# IMD_AMS_Latch.net
KiCad netlist of a schematic drawn in EAGLE
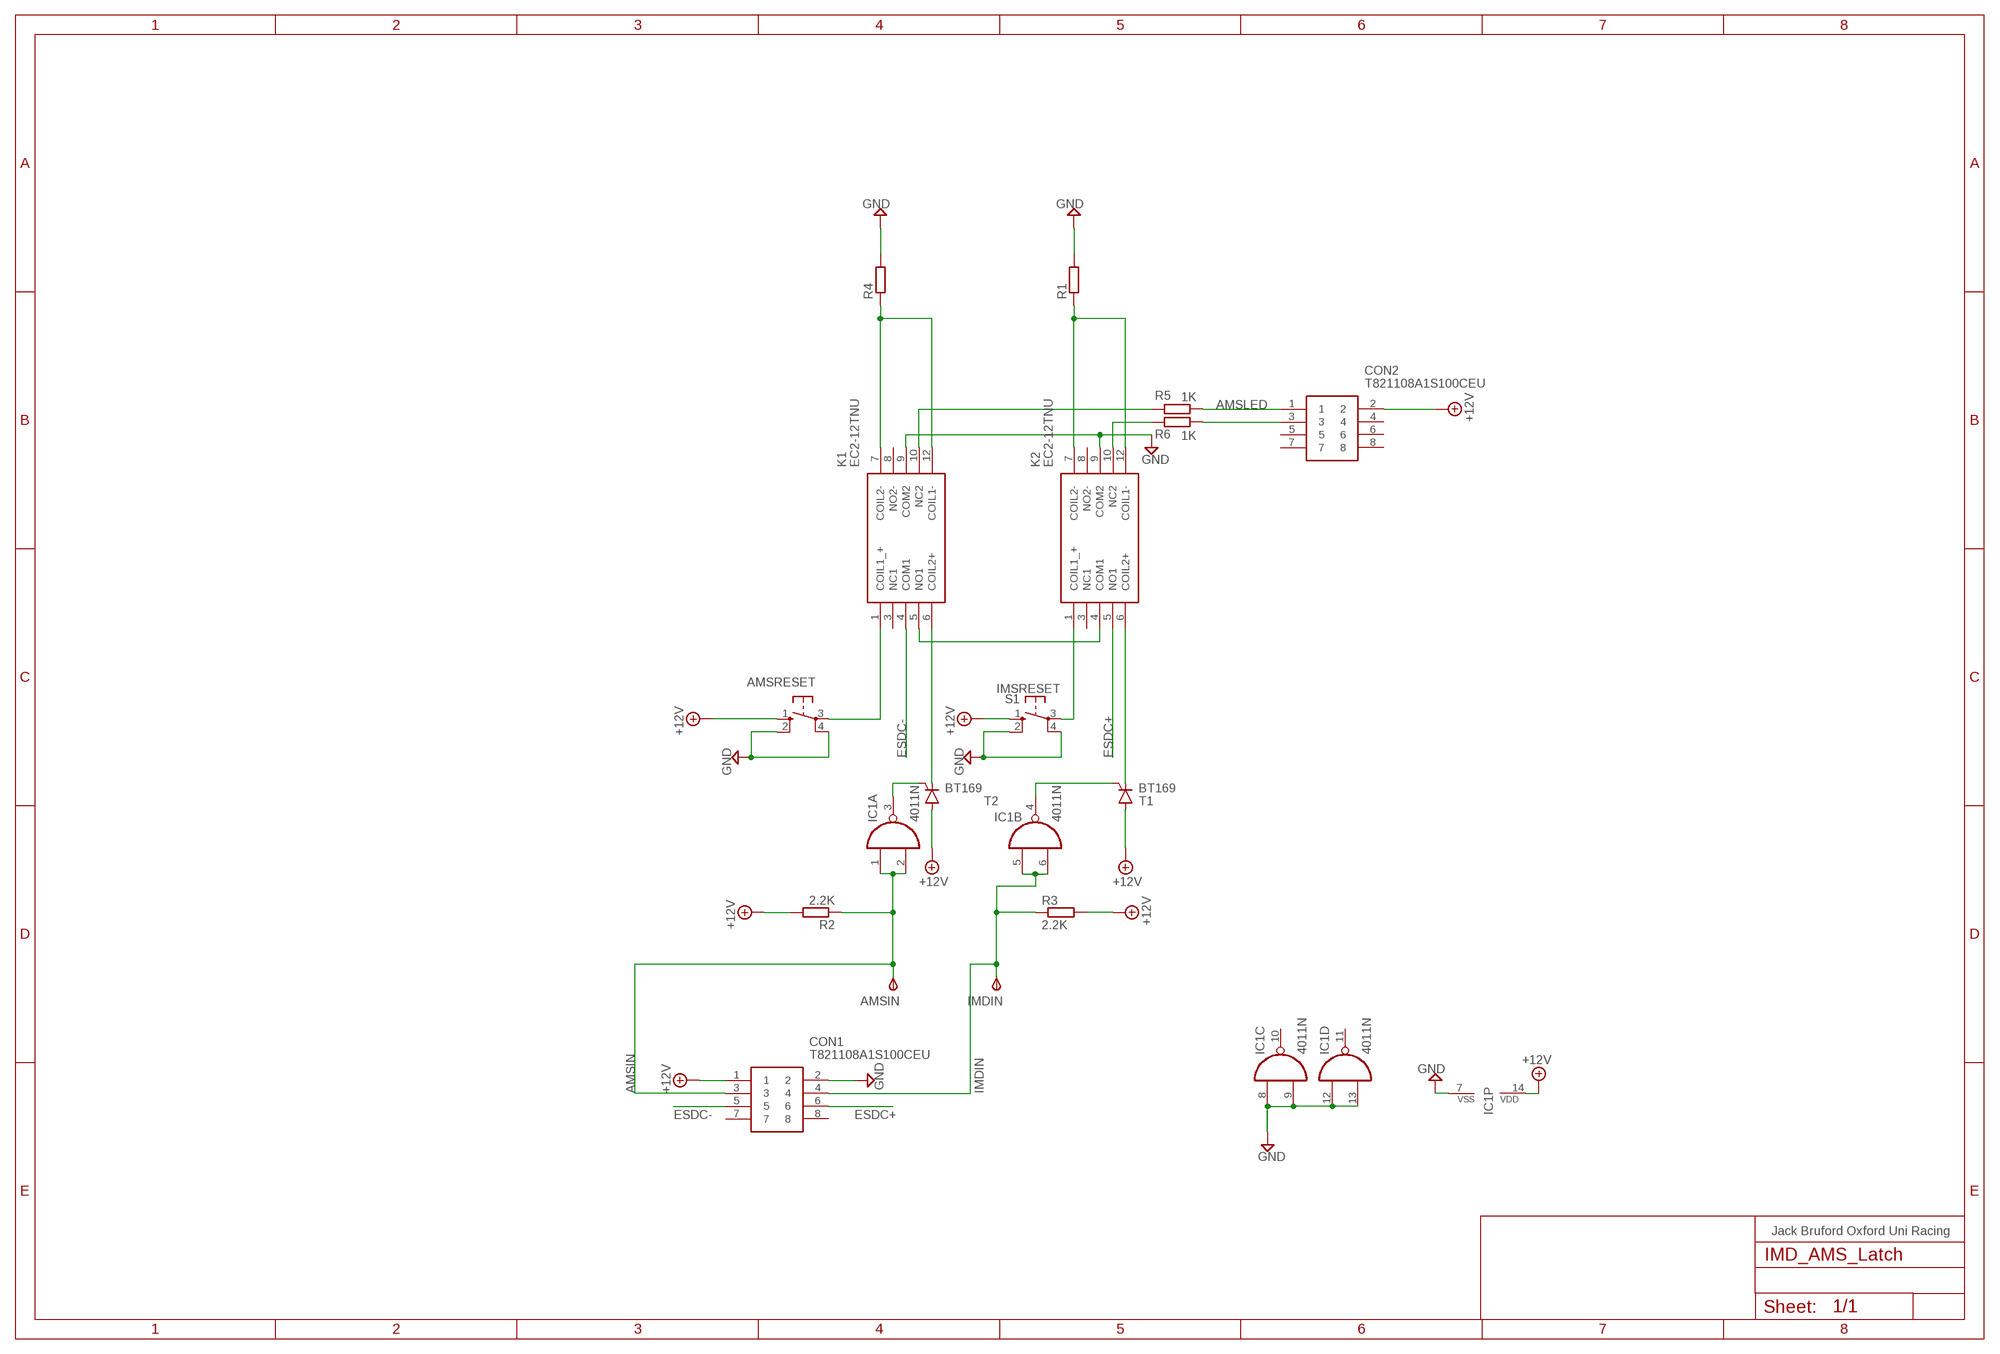
[diagram p0: schematic, sheet 1]

(export (version "E")
  (design (tool "Eeschema 10.0.6"))
  (components
    (comp (ref "AMSIN")
      (value "TPSPAD1-13")
      (footprint "eagle-import:P1-13")
      (libsource (lib "eagle-import") (part "TPSPAD1-13"))
    )
    (comp (ref "AMSRESET")
      (value "10-XX")
      (footprint "eagle-import:B3F-10XX")
      (fields (field (name "MPN") "B3F-1000"))
      (libsource (lib "eagle-import") (part "10-XX"))
    )
    (comp (ref "CON1")
      (value "T821108A1S100CEU")
      (footprint "eagle-import:HDRV8W64P254_2X4_1778X895X915P")
      (fields (field (name "RS_PART_NUMBER") "1702738"))
      (libsource (lib "eagle-import") (part "T821108A1S100CEU"))
    )
    (comp (ref "CON2")
      (value "T821108A1S100CEU")
      (footprint "eagle-import:HDRV8W64P254_2X4_1778X895X915P")
      (fields (field (name "RS_PART_NUMBER") "1702738"))
      (libsource (lib "eagle-import") (part "T821108A1S100CEU"))
    )
    (comp (ref "IC1")
      (value "4011N")
      (footprint "eagle-import:DIL14")
      (libsource (lib "eagle-import") (part "4011N"))
    )
    (comp (ref "IMDIN")
      (value "TPSPAD1-13")
      (footprint "eagle-import:P1-13")
      (libsource (lib "eagle-import") (part "TPSPAD1-13"))
    )
    (comp (ref "K1")
      (value "EC2-12TNU")
      (footprint "eagle-import:EC212TNU")
      (fields (field (name "MOUSER_PART_NUMBER") "80-EC2-12TNU"))
      (libsource (lib "eagle-import") (part "EC2-12TNU"))
    )
    (comp (ref "K2")
      (value "EC2-12TNU")
      (footprint "eagle-import:EC212TNU")
      (fields (field (name "MOUSER_PART_NUMBER") "80-EC2-12TNU"))
      (libsource (lib "eagle-import") (part "EC2-12TNU"))
    )
    (comp (ref "R1")
      (value "R-EU_0207/15")
      (footprint "eagle-import:0207_15")
      (libsource (lib "eagle-import") (part "R-EU_0207/15"))
    )
    (comp (ref "R2")
      (value "2.2K")
      (footprint "eagle-import:0207_15")
      (libsource (lib "eagle-import") (part "R-EU_0207/15"))
    )
    (comp (ref "R3")
      (value "2.2K")
      (footprint "eagle-import:0207_15")
      (libsource (lib "eagle-import") (part "R-EU_0207/15"))
    )
    (comp (ref "R4")
      (value "R-EU_0207/15")
      (footprint "eagle-import:0207_15")
      (libsource (lib "eagle-import") (part "R-EU_0207/15"))
    )
    (comp (ref "R5")
      (value "1K")
      (footprint "eagle-import:0207_15")
      (libsource (lib "eagle-import") (part "R-EU_0207/15"))
    )
    (comp (ref "R6")
      (value "1K")
      (footprint "eagle-import:0207_15")
      (libsource (lib "eagle-import") (part "R-EU_0207/15"))
    )
    (comp (ref "S1")
      (value "10-XX")
      (footprint "eagle-import:B3F-10XX")
      (fields (field (name "MPN") "B3F-1000"))
      (libsource (lib "eagle-import") (part "10-XX"))
    )
    (comp (ref "T1")
      (value "BT169")
      (footprint "eagle-import:TO92-2")
      (libsource (lib "eagle-import") (part "BT169"))
    )
    (comp (ref "T2")
      (value "BT169")
      (footprint "eagle-import:TO92-2")
      (libsource (lib "eagle-import") (part "BT169"))
    )
  )
  (nets
    (net (code "1") (name "+12V") (class "Default")
      (node (ref "AMSRESET") (pin "1") (pinfunction "S_1") (pintype "passive"))
      (node (ref "CON1") (pin "1") (pinfunction "1_1") (pintype "bidirectional"))
      (node (ref "CON2") (pin "2") (pinfunction "2_2") (pintype "bidirectional"))
      (node (ref "IC1") (pin "14") (pinfunction "VDD_14") (pintype "power_in"))
      (node (ref "R2") (pin "2") (pinfunction "2_2") (pintype "passive"))
      (node (ref "R3") (pin "2") (pinfunction "2_2") (pintype "passive"))
      (node (ref "S1") (pin "1") (pinfunction "S_1") (pintype "passive"))
      (node (ref "T1") (pin "A") (pinfunction "A_A") (pintype "passive"))
      (node (ref "T2") (pin "A") (pinfunction "A_A") (pintype "passive"))
    )
    (net (code "2") (name "/AMSIN") (class "Default")
      (node (ref "AMSIN") (pin "TP") (pinfunction "PP_TP") (pintype "input"))
      (node (ref "CON1") (pin "3") (pinfunction "3_3") (pintype "bidirectional"))
      (node (ref "IC1") (pin "1") (pinfunction "I0_1") (pintype "input"))
      (node (ref "IC1") (pin "2") (pinfunction "I1_2") (pintype "input"))
      (node (ref "R2") (pin "1") (pinfunction "1_1") (pintype "passive"))
    )
    (net (code "3") (name "/AMSLED") (class "Default")
      (node (ref "K1") (pin "10") (pinfunction "NC2_10") (pintype "bidirectional"))
      (node (ref "R5") (pin "2") (pinfunction "2_2") (pintype "passive"))
    )
    (net (code "4") (name "/ESDC+") (class "Default")
      (node (ref "CON1") (pin "6") (pinfunction "6_6") (pintype "bidirectional"))
      (node (ref "K2") (pin "5") (pinfunction "NO1_5") (pintype "bidirectional"))
    )
    (net (code "5") (name "/ESDC-") (class "Default")
      (node (ref "CON1") (pin "5") (pinfunction "5_5") (pintype "bidirectional"))
      (node (ref "K1") (pin "4") (pinfunction "COM1_4") (pintype "bidirectional"))
    )
    (net (code "6") (name "/IMDIN") (class "Default")
      (node (ref "CON1") (pin "4") (pinfunction "4_4") (pintype "bidirectional"))
      (node (ref "IC1") (pin "5") (pinfunction "I0_5") (pintype "input"))
      (node (ref "IC1") (pin "6") (pinfunction "I1_6") (pintype "input"))
      (node (ref "IMDIN") (pin "TP") (pinfunction "PP_TP") (pintype "input"))
      (node (ref "R3") (pin "1") (pinfunction "1_1") (pintype "passive"))
    )
    (net (code "7") (name "/IMSRESET") (class "Default")
      (node (ref "K1") (pin "5") (pinfunction "NO1_5") (pintype "bidirectional"))
      (node (ref "K2") (pin "4") (pinfunction "COM1_4") (pintype "bidirectional"))
    )
    (net (code "8") (name "GND") (class "Default")
      (node (ref "AMSRESET") (pin "2") (pinfunction "S1_2") (pintype "passive"))
      (node (ref "AMSRESET") (pin "4") (pinfunction "P1_4") (pintype "passive"))
      (node (ref "CON1") (pin "2") (pinfunction "2_2") (pintype "bidirectional"))
      (node (ref "IC1") (pin "12") (pinfunction "I0_12") (pintype "input"))
      (node (ref "IC1") (pin "13") (pinfunction "I1_13") (pintype "input"))
      (node (ref "IC1") (pin "7") (pinfunction "VSS_7") (pintype "power_in"))
      (node (ref "IC1") (pin "8") (pinfunction "I0_8") (pintype "input"))
      (node (ref "IC1") (pin "9") (pinfunction "I1_9") (pintype "input"))
      (node (ref "K1") (pin "9") (pinfunction "COM2_9") (pintype "bidirectional"))
      (node (ref "K2") (pin "9") (pinfunction "COM2_9") (pintype "bidirectional"))
      (node (ref "R1") (pin "2") (pinfunction "2_2") (pintype "passive"))
      (node (ref "R4") (pin "2") (pinfunction "2_2") (pintype "passive"))
      (node (ref "S1") (pin "2") (pinfunction "S1_2") (pintype "passive"))
      (node (ref "S1") (pin "4") (pinfunction "P1_4") (pintype "passive"))
    )
    (net (code "9") (name "Net-(AMSRESET-P)") (class "Default")
      (node (ref "AMSRESET") (pin "3") (pinfunction "P_3") (pintype "passive"))
      (node (ref "K1") (pin "1") (pinfunction "COIL1_+_1") (pintype "bidirectional"))
    )
    (net (code "10") (name "Net-(CON2-Pad1)") (class "Default")
      (node (ref "CON2") (pin "1") (pinfunction "1_1") (pintype "bidirectional"))
      (node (ref "R5") (pin "1") (pinfunction "1_1") (pintype "passive"))
    )
    (net (code "11") (name "Net-(CON2-Pad3)") (class "Default")
      (node (ref "CON2") (pin "3") (pinfunction "3_3") (pintype "bidirectional"))
      (node (ref "R6") (pin "1") (pinfunction "1_1") (pintype "passive"))
    )
    (net (code "12") (name "Net-(IC1A-O)") (class "Default")
      (node (ref "IC1") (pin "3") (pinfunction "O_3") (pintype "output"))
      (node (ref "T2") (pin "G") (pinfunction "G_G") (pintype "passive"))
    )
    (net (code "13") (name "Net-(IC1B-O)") (class "Default")
      (node (ref "IC1") (pin "4") (pinfunction "O_4") (pintype "output"))
      (node (ref "T1") (pin "G") (pinfunction "G_G") (pintype "passive"))
    )
    (net (code "14") (name "Net-(K1-COIL1-)") (class "Default")
      (node (ref "K1") (pin "12") (pinfunction "COIL1-_12") (pintype "bidirectional"))
      (node (ref "K1") (pin "7") (pinfunction "COIL2-_7") (pintype "bidirectional"))
      (node (ref "R4") (pin "1") (pinfunction "1_1") (pintype "passive"))
    )
    (net (code "15") (name "Net-(K1-COIL2+)") (class "Default")
      (node (ref "K1") (pin "6") (pinfunction "COIL2+_6") (pintype "bidirectional"))
      (node (ref "T2") (pin "C") (pinfunction "C_C") (pintype "passive"))
    )
    (net (code "16") (name "Net-(K2-COIL1-)") (class "Default")
      (node (ref "K2") (pin "12") (pinfunction "COIL1-_12") (pintype "bidirectional"))
      (node (ref "K2") (pin "7") (pinfunction "COIL2-_7") (pintype "bidirectional"))
      (node (ref "R1") (pin "1") (pinfunction "1_1") (pintype "passive"))
    )
    (net (code "17") (name "Net-(K2-COIL1_+)") (class "Default")
      (node (ref "K2") (pin "1") (pinfunction "COIL1_+_1") (pintype "bidirectional"))
      (node (ref "S1") (pin "3") (pinfunction "P_3") (pintype "passive"))
    )
    (net (code "18") (name "Net-(K2-COIL2+)") (class "Default")
      (node (ref "K2") (pin "6") (pinfunction "COIL2+_6") (pintype "bidirectional"))
      (node (ref "T1") (pin "C") (pinfunction "C_C") (pintype "passive"))
    )
    (net (code "19") (name "Net-(K2-NC2)") (class "Default")
      (node (ref "K2") (pin "10") (pinfunction "NC2_10") (pintype "bidirectional"))
      (node (ref "R6") (pin "2") (pinfunction "2_2") (pintype "passive"))
    )
    (net (code "20") (name "unconnected-(CON1-Pad7)") (class "Default")
      (node (ref "CON1") (pin "7") (pinfunction "7_7") (pintype "bidirectional"))
    )
    (net (code "21") (name "unconnected-(CON1-Pad8)") (class "Default")
      (node (ref "CON1") (pin "8") (pinfunction "8_8") (pintype "bidirectional"))
    )
    (net (code "22") (name "unconnected-(CON2-Pad4)") (class "Default")
      (node (ref "CON2") (pin "4") (pinfunction "4_4") (pintype "bidirectional"))
    )
    (net (code "23") (name "unconnected-(CON2-Pad5)") (class "Default")
      (node (ref "CON2") (pin "5") (pinfunction "5_5") (pintype "bidirectional"))
    )
    (net (code "24") (name "unconnected-(CON2-Pad6)") (class "Default")
      (node (ref "CON2") (pin "6") (pinfunction "6_6") (pintype "bidirectional"))
    )
    (net (code "25") (name "unconnected-(CON2-Pad7)") (class "Default")
      (node (ref "CON2") (pin "7") (pinfunction "7_7") (pintype "bidirectional"))
    )
    (net (code "26") (name "unconnected-(CON2-Pad8)") (class "Default")
      (node (ref "CON2") (pin "8") (pinfunction "8_8") (pintype "bidirectional"))
    )
    (net (code "27") (name "unconnected-(IC1C-O-Pad10)") (class "Default")
      (node (ref "IC1") (pin "10") (pinfunction "O_10") (pintype "output"))
    )
    (net (code "28") (name "unconnected-(IC1D-O-Pad11)") (class "Default")
      (node (ref "IC1") (pin "11") (pinfunction "O_11") (pintype "output"))
    )
    (net (code "29") (name "unconnected-(K1-NC1-Pad3)") (class "Default")
      (node (ref "K1") (pin "3") (pinfunction "NC1_3") (pintype "bidirectional"))
    )
    (net (code "30") (name "unconnected-(K1-NO2--Pad8)") (class "Default")
      (node (ref "K1") (pin "8") (pinfunction "NO2-_8") (pintype "bidirectional"))
    )
    (net (code "31") (name "unconnected-(K2-NC1-Pad3)") (class "Default")
      (node (ref "K2") (pin "3") (pinfunction "NC1_3") (pintype "bidirectional"))
    )
    (net (code "32") (name "unconnected-(K2-NO2--Pad8)") (class "Default")
      (node (ref "K2") (pin "8") (pinfunction "NO2-_8") (pintype "bidirectional"))
    )
  )
)
